# ChargerTimer_V5.net
KiCad netlist of a schematic drawn in EAGLE
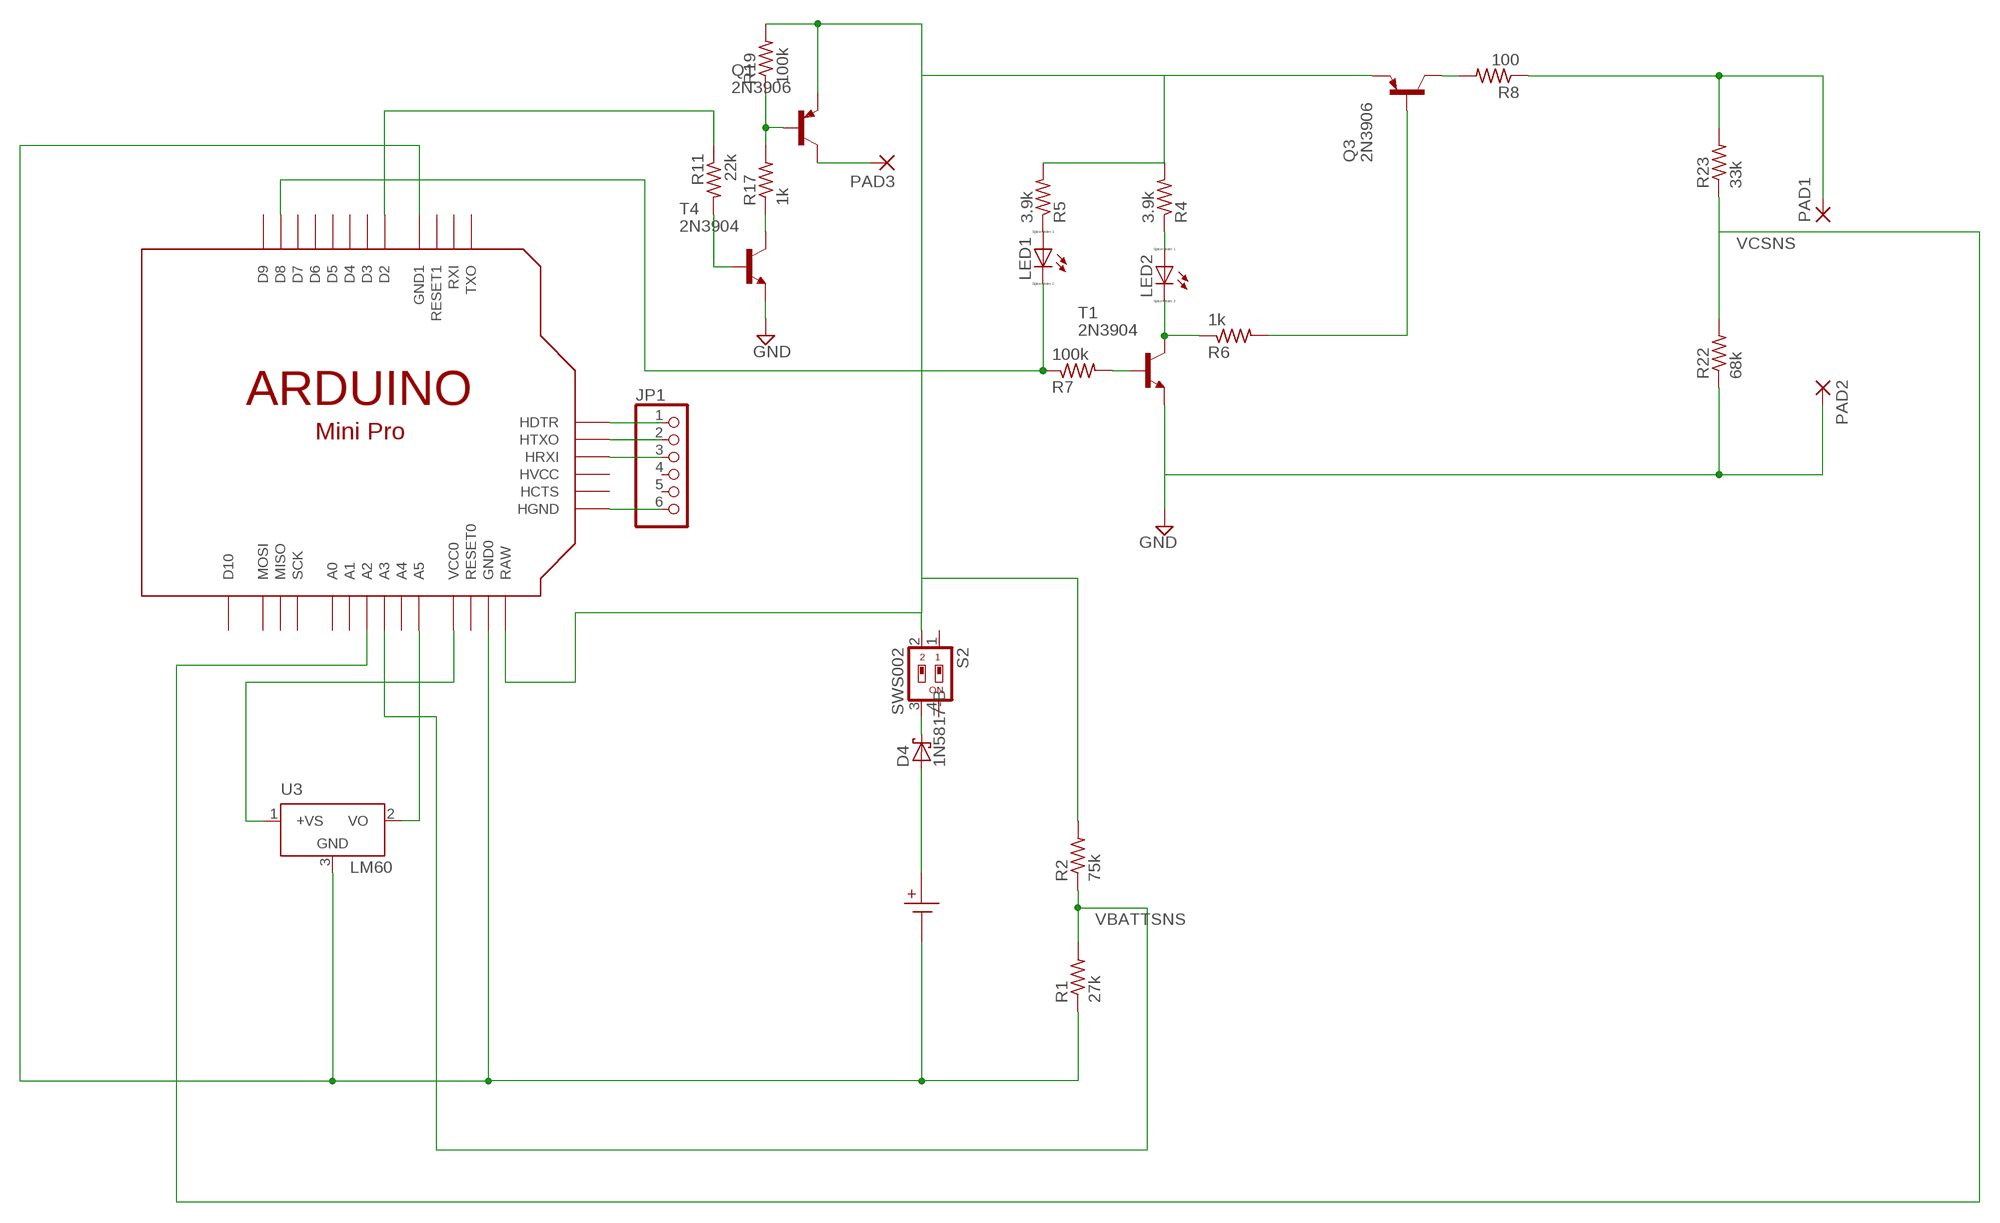
[diagram p0: schematic, sheet 1]

(export (version "E")
  (design (tool "Eeschema 10.0.6"))
  (components
    (comp (ref "D4")
      (value "1N5817-B")
      (footprint "eagle-import:DO41-7.6")
      (libsource (lib "eagle-import") (part "1N5817-B"))
    )
    (comp (ref "JP1")
      (value "PINHD-1X6")
      (footprint "eagle-import:1X06")
      (libsource (lib "eagle-import") (part "PINHD-1X6"))
    )
    (comp (ref "LED1")
      (value "LED_ELD260")
      (footprint "eagle-import:LED_LD260")
      (libsource (lib "eagle-import") (part "LED_ELD260"))
    )
    (comp (ref "LED2")
      (value "LED_ELD260")
      (footprint "eagle-import:LED_LD260")
      (libsource (lib "eagle-import") (part "LED_ELD260"))
    )
    (comp (ref "PAD1")
      (value "2,15/1,0")
      (footprint "eagle-import:2,15_1,0")
      (libsource (lib "eagle-import") (part "2,15/1,0"))
    )
    (comp (ref "PAD2")
      (value "2,15/1,0")
      (footprint "eagle-import:2,15_1,0")
      (libsource (lib "eagle-import") (part "2,15/1,0"))
    )
    (comp (ref "PAD3")
      (value "2,15/1,0")
      (footprint "eagle-import:2,15_1,0")
      (libsource (lib "eagle-import") (part "2,15/1,0"))
    )
    (comp (ref "Q1")
      (value "2N3906")
      (footprint "eagle-import:TO92")
      (libsource (lib "eagle-import") (part "2N3906"))
    )
    (comp (ref "Q3")
      (value "2N3906")
      (footprint "eagle-import:TO92")
      (libsource (lib "eagle-import") (part "2N3906"))
    )
    (comp (ref "R1")
      (value "27k")
      (footprint "eagle-import:0207_7")
      (libsource (lib "eagle-import") (part "R-US_0207/7"))
    )
    (comp (ref "R2")
      (value "75k")
      (footprint "eagle-import:0207_7")
      (libsource (lib "eagle-import") (part "R-US_0207/7"))
    )
    (comp (ref "R4")
      (value "3.9k")
      (footprint "eagle-import:0207_7")
      (libsource (lib "eagle-import") (part "R-US_0207/7"))
    )
    (comp (ref "R5")
      (value "3.9k")
      (footprint "eagle-import:0207_7")
      (libsource (lib "eagle-import") (part "R-US_0207/7"))
    )
    (comp (ref "R6")
      (value "1k")
      (footprint "eagle-import:0207_7")
      (libsource (lib "eagle-import") (part "R-US_0207/7"))
    )
    (comp (ref "R7")
      (value "100k")
      (footprint "eagle-import:0207_7")
      (libsource (lib "eagle-import") (part "R-US_0207/7"))
    )
    (comp (ref "R8")
      (value "100")
      (footprint "eagle-import:0207_7")
      (libsource (lib "eagle-import") (part "R-US_0207/7"))
    )
    (comp (ref "R11")
      (value "22k")
      (footprint "eagle-import:0207_7")
      (libsource (lib "eagle-import") (part "R-US_0207/7"))
    )
    (comp (ref "R17")
      (value "1k")
      (footprint "eagle-import:0207_7")
      (libsource (lib "eagle-import") (part "R-US_0207/7"))
    )
    (comp (ref "R19")
      (value "100k")
      (footprint "eagle-import:0207_7")
      (libsource (lib "eagle-import") (part "R-US_0207/7"))
    )
    (comp (ref "R22")
      (value "68k")
      (footprint "eagle-import:0207_7")
      (libsource (lib "eagle-import") (part "R-US_0207/7"))
    )
    (comp (ref "R23")
      (value "33k")
      (footprint "eagle-import:0207_7")
      (libsource (lib "eagle-import") (part "R-US_0207/7"))
    )
    (comp (ref "S2")
      (value "SWS002")
      (footprint "eagle-import:SMS-002")
      (libsource (lib "eagle-import") (part "SWS002"))
    )
    (comp (ref "T1")
      (value "2N3904")
      (footprint "eagle-import:TO92")
      (libsource (lib "eagle-import") (part "2N3904"))
    )
    (comp (ref "T4")
      (value "2N3904")
      (footprint "eagle-import:TO92")
      (libsource (lib "eagle-import") (part "2N3904"))
    )
    (comp (ref "U$1")
      (value "BH1000G")
      (footprint "eagle-import:BH1000G")
      (libsource (lib "eagle-import") (part "BH1000G"))
    )
    (comp (ref "U$4")
      (value "ARDUINOMINI")
      (footprint "eagle-import:ARDUINOMINI")
      (libsource (lib "eagle-import") (part "ARDUINOMINI"))
    )
    (comp (ref "U3")
      (value "LM60")
      (footprint "eagle-import:TO92")
      (libsource (lib "eagle-import") (part "LM60"))
    )
  )
  (nets
    (net (code "1") (name "/VBATTSNS") (class "Default")
      (node (ref "R1") (pin "2") (pinfunction "2_2") (pintype "passive"))
      (node (ref "R2") (pin "1") (pinfunction "1_1") (pintype "passive"))
      (node (ref "U$4") (pin "P$23") (pinfunction "A3_P$23") (pintype "bidirectional"))
    )
    (net (code "2") (name "/VCSNS") (class "Default")
      (node (ref "R22") (pin "2") (pinfunction "2_2") (pintype "passive"))
      (node (ref "R23") (pin "1") (pinfunction "1_1") (pintype "passive"))
      (node (ref "U$4") (pin "P$24") (pinfunction "A2_P$24") (pintype "bidirectional"))
    )
    (net (code "3") (name "GND") (class "Default")
      (node (ref "T1") (pin "3") (pinfunction "E_3") (pintype "passive"))
      (node (ref "T4") (pin "3") (pinfunction "E_3") (pintype "passive"))
    )
    (net (code "4") (name "Net-(D4-PadC)") (class "Default")
      (node (ref "D4") (pin "C") (pinfunction "C_C") (pintype "passive"))
      (node (ref "S2") (pin "3") (pinfunction "3_3") (pintype "passive"))
    )
    (net (code "5") (name "Net-(LED1-C)") (class "Default")
      (node (ref "LED1") (pin "K") (pinfunction "C_K") (pintype "passive"))
      (node (ref "R7") (pin "1") (pinfunction "1_1") (pintype "passive"))
      (node (ref "U$4") (pin "P$2") (pinfunction "D8_P$2") (pintype "bidirectional"))
    )
    (net (code "6") (name "Net-(LED1-PadA)") (class "Default")
      (node (ref "LED1") (pin "A") (pinfunction "A_A") (pintype "passive"))
      (node (ref "R5") (pin "1") (pinfunction "1_1") (pintype "passive"))
    )
    (net (code "7") (name "Net-(LED2-C)") (class "Default")
      (node (ref "LED2") (pin "K") (pinfunction "C_K") (pintype "passive"))
      (node (ref "R6") (pin "1") (pinfunction "1_1") (pintype "passive"))
      (node (ref "T1") (pin "1") (pinfunction "C_1") (pintype "passive"))
    )
    (net (code "8") (name "Net-(LED2-PadA)") (class "Default")
      (node (ref "LED2") (pin "A") (pinfunction "A_A") (pintype "passive"))
      (node (ref "R4") (pin "1") (pinfunction "1_1") (pintype "passive"))
    )
    (net (code "9") (name "Net-(PAD1-P)") (class "Default")
      (node (ref "PAD1") (pin "1") (pinfunction "P_1") (pintype "passive"))
      (node (ref "R23") (pin "2") (pinfunction "2_2") (pintype "passive"))
      (node (ref "R8") (pin "1") (pinfunction "1_1") (pintype "passive"))
    )
    (net (code "10") (name "Net-(PAD2-P)") (class "Default")
      (node (ref "PAD2") (pin "1") (pinfunction "P_1") (pintype "passive"))
      (node (ref "R22") (pin "1") (pinfunction "1_1") (pintype "passive"))
    )
    (net (code "11") (name "Net-(PAD3-P)") (class "Default")
      (node (ref "PAD3") (pin "1") (pinfunction "P_1") (pintype "passive"))
      (node (ref "Q1") (pin "1") (pinfunction "C_1") (pintype "passive"))
    )
    (net (code "12") (name "Net-(Q1-B)") (class "Default")
      (node (ref "Q1") (pin "2") (pinfunction "B_2") (pintype "passive"))
      (node (ref "R17") (pin "2") (pinfunction "2_2") (pintype "passive"))
      (node (ref "R19") (pin "1") (pinfunction "1_1") (pintype "passive"))
    )
    (net (code "13") (name "Net-(Q1-E)") (class "Default")
      (node (ref "Q1") (pin "3") (pinfunction "E_3") (pintype "passive"))
      (node (ref "Q3") (pin "3") (pinfunction "E_3") (pintype "passive"))
      (node (ref "R19") (pin "2") (pinfunction "2_2") (pintype "passive"))
      (node (ref "R2") (pin "2") (pinfunction "2_2") (pintype "passive"))
      (node (ref "R4") (pin "2") (pinfunction "2_2") (pintype "passive"))
      (node (ref "R5") (pin "2") (pinfunction "2_2") (pintype "passive"))
      (node (ref "S2") (pin "2") (pinfunction "2_2") (pintype "passive"))
      (node (ref "U$4") (pin "P$19") (pinfunction "RAW_P$19") (pintype "bidirectional"))
    )
    (net (code "14") (name "Net-(Q3-B)") (class "Default")
      (node (ref "Q3") (pin "2") (pinfunction "B_2") (pintype "passive"))
      (node (ref "R6") (pin "2") (pinfunction "2_2") (pintype "passive"))
    )
    (net (code "15") (name "Net-(Q3-C)") (class "Default")
      (node (ref "Q3") (pin "1") (pinfunction "C_1") (pintype "passive"))
      (node (ref "R8") (pin "2") (pinfunction "2_2") (pintype "passive"))
    )
    (net (code "16") (name "Net-(T1-B)") (class "Default")
      (node (ref "R7") (pin "2") (pinfunction "2_2") (pintype "passive"))
      (node (ref "T1") (pin "2") (pinfunction "B_2") (pintype "passive"))
    )
    (net (code "17") (name "Net-(T4-B)") (class "Default")
      (node (ref "R11") (pin "2") (pinfunction "2_2") (pintype "passive"))
      (node (ref "T4") (pin "2") (pinfunction "B_2") (pintype "passive"))
    )
    (net (code "18") (name "Net-(T4-C)") (class "Default")
      (node (ref "R17") (pin "1") (pinfunction "1_1") (pintype "passive"))
      (node (ref "T4") (pin "1") (pinfunction "C_1") (pintype "passive"))
    )
    (net (code "19") (name "Net-(U$1-P1)") (class "Default")
      (node (ref "D4") (pin "A") (pinfunction "A_A") (pintype "passive"))
      (node (ref "U$1") (pin "POS$1") (pinfunction "P1_POS$1") (pintype "power_in"))
    )
    (net (code "20") (name "Net-(U$1-P2)") (class "Default")
      (node (ref "R1") (pin "1") (pinfunction "1_1") (pintype "passive"))
      (node (ref "U$1") (pin "NEG$2") (pinfunction "P2_NEG$2") (pintype "power_in"))
      (node (ref "U$4") (pin "P$20") (pinfunction "GND0_P$20") (pintype "bidirectional"))
      (node (ref "U$4") (pin "P$9") (pinfunction "GND1_P$9") (pintype "bidirectional"))
      (node (ref "U3") (pin "3") (pinfunction "GND_3") (pintype "power_in"))
    )
    (net (code "21") (name "Net-(U$4-A5)") (class "Default")
      (node (ref "U$4") (pin "P$35") (pinfunction "A5_P$35") (pintype "bidirectional"))
      (node (ref "U3") (pin "2") (pinfunction "VO_2") (pintype "input"))
    )
    (net (code "22") (name "Net-(U$4-D2)") (class "Default")
      (node (ref "R11") (pin "1") (pinfunction "1_1") (pintype "passive"))
      (node (ref "U$4") (pin "P$8") (pinfunction "D2_P$8") (pintype "bidirectional"))
    )
    (net (code "23") (name "Net-(U$4-HDTR)") (class "Default")
      (node (ref "JP1") (pin "1") (pinfunction "1_1") (pintype "passive"))
      (node (ref "U$4") (pin "P$13") (pinfunction "HDTR_P$13") (pintype "bidirectional"))
    )
    (net (code "24") (name "Net-(U$4-HGND)") (class "Default")
      (node (ref "JP1") (pin "6") (pinfunction "6_6") (pintype "passive"))
      (node (ref "U$4") (pin "P$18") (pinfunction "HGND_P$18") (pintype "bidirectional"))
    )
    (net (code "25") (name "Net-(U$4-HRXI)") (class "Default")
      (node (ref "JP1") (pin "3") (pinfunction "3_3") (pintype "passive"))
      (node (ref "U$4") (pin "P$15") (pinfunction "HRXI_P$15") (pintype "bidirectional"))
    )
    (net (code "26") (name "Net-(U$4-HTXO)") (class "Default")
      (node (ref "JP1") (pin "2") (pinfunction "2_2") (pintype "passive"))
      (node (ref "U$4") (pin "P$14") (pinfunction "HTXO_P$14") (pintype "bidirectional"))
    )
    (net (code "27") (name "Net-(U$4-VCC0)") (class "Default")
      (node (ref "U$4") (pin "P$22") (pinfunction "VCC0_P$22") (pintype "bidirectional"))
      (node (ref "U3") (pin "1") (pinfunction "+VS_1") (pintype "input"))
    )
    (net (code "28") (name "unconnected-(JP1-Pad4)") (class "Default")
      (node (ref "JP1") (pin "4") (pinfunction "4_4") (pintype "passive"))
    )
    (net (code "29") (name "unconnected-(JP1-Pad5)") (class "Default")
      (node (ref "JP1") (pin "5") (pinfunction "5_5") (pintype "passive"))
    )
    (net (code "30") (name "unconnected-(S2-Pad1)") (class "Default")
      (node (ref "S2") (pin "1") (pinfunction "1_1") (pintype "passive"))
    )
    (net (code "31") (name "unconnected-(S2-Pad4)") (class "Default")
      (node (ref "S2") (pin "4") (pinfunction "4_4") (pintype "passive"))
    )
    (net (code "32") (name "unconnected-(U$4-A0-PadP$26)") (class "Default")
      (node (ref "U$4") (pin "P$26") (pinfunction "A0_P$26") (pintype "bidirectional"))
    )
    (net (code "33") (name "unconnected-(U$4-A1-PadP$25)") (class "Default")
      (node (ref "U$4") (pin "P$25") (pinfunction "A1_P$25") (pintype "bidirectional"))
    )
    (net (code "34") (name "unconnected-(U$4-A4-PadP$34)") (class "Default")
      (node (ref "U$4") (pin "P$34") (pinfunction "A4_P$34") (pintype "bidirectional"))
    )
    (net (code "35") (name "unconnected-(U$4-D3-PadP$7)") (class "Default")
      (node (ref "U$4") (pin "P$7") (pinfunction "D3_P$7") (pintype "bidirectional"))
    )
    (net (code "36") (name "unconnected-(U$4-D4-PadP$6)") (class "Default")
      (node (ref "U$4") (pin "P$6") (pinfunction "D4_P$6") (pintype "bidirectional"))
    )
    (net (code "37") (name "unconnected-(U$4-D5-PadP$5)") (class "Default")
      (node (ref "U$4") (pin "P$5") (pinfunction "D5_P$5") (pintype "bidirectional"))
    )
    (net (code "38") (name "unconnected-(U$4-D6-PadP$4)") (class "Default")
      (node (ref "U$4") (pin "P$4") (pinfunction "D6_P$4") (pintype "bidirectional"))
    )
    (net (code "39") (name "unconnected-(U$4-D7-PadP$3)") (class "Default")
      (node (ref "U$4") (pin "P$3") (pinfunction "D7_P$3") (pintype "bidirectional"))
    )
    (net (code "40") (name "unconnected-(U$4-D9-PadP$1)") (class "Default")
      (node (ref "U$4") (pin "P$1") (pinfunction "D9_P$1") (pintype "bidirectional"))
    )
    (net (code "41") (name "unconnected-(U$4-D10-PadP$30)") (class "Default")
      (node (ref "U$4") (pin "P$30") (pinfunction "D10_P$30") (pintype "bidirectional"))
    )
    (net (code "42") (name "unconnected-(U$4-HCTS-PadP$17)") (class "Default")
      (node (ref "U$4") (pin "P$17") (pinfunction "HCTS_P$17") (pintype "bidirectional"))
    )
    (net (code "43") (name "unconnected-(U$4-HVCC-PadP$16)") (class "Default")
      (node (ref "U$4") (pin "P$16") (pinfunction "HVCC_P$16") (pintype "bidirectional"))
    )
    (net (code "44") (name "unconnected-(U$4-MISO-PadP$28)") (class "Default")
      (node (ref "U$4") (pin "P$28") (pinfunction "MISO_P$28") (pintype "bidirectional"))
    )
    (net (code "45") (name "unconnected-(U$4-MOSI-PadP$29)") (class "Default")
      (node (ref "U$4") (pin "P$29") (pinfunction "MOSI_P$29") (pintype "bidirectional"))
    )
    (net (code "46") (name "unconnected-(U$4-RESET0-PadP$21)") (class "Default")
      (node (ref "U$4") (pin "P$21") (pinfunction "RESET0_P$21") (pintype "bidirectional"))
    )
    (net (code "47") (name "unconnected-(U$4-RESET1-PadP$10)") (class "Default")
      (node (ref "U$4") (pin "P$10") (pinfunction "RESET1_P$10") (pintype "bidirectional"))
    )
    (net (code "48") (name "unconnected-(U$4-RXI-PadP$11)") (class "Default")
      (node (ref "U$4") (pin "P$11") (pinfunction "RXI_P$11") (pintype "bidirectional"))
    )
    (net (code "49") (name "unconnected-(U$4-SCK-PadP$27)") (class "Default")
      (node (ref "U$4") (pin "P$27") (pinfunction "SCK_P$27") (pintype "bidirectional"))
    )
    (net (code "50") (name "unconnected-(U$4-TXO-PadP$12)") (class "Default")
      (node (ref "U$4") (pin "P$12") (pinfunction "TXO_P$12") (pintype "bidirectional"))
    )
  )
)
